# 2.net
KiCad netlist of a schematic drawn in EAGLE
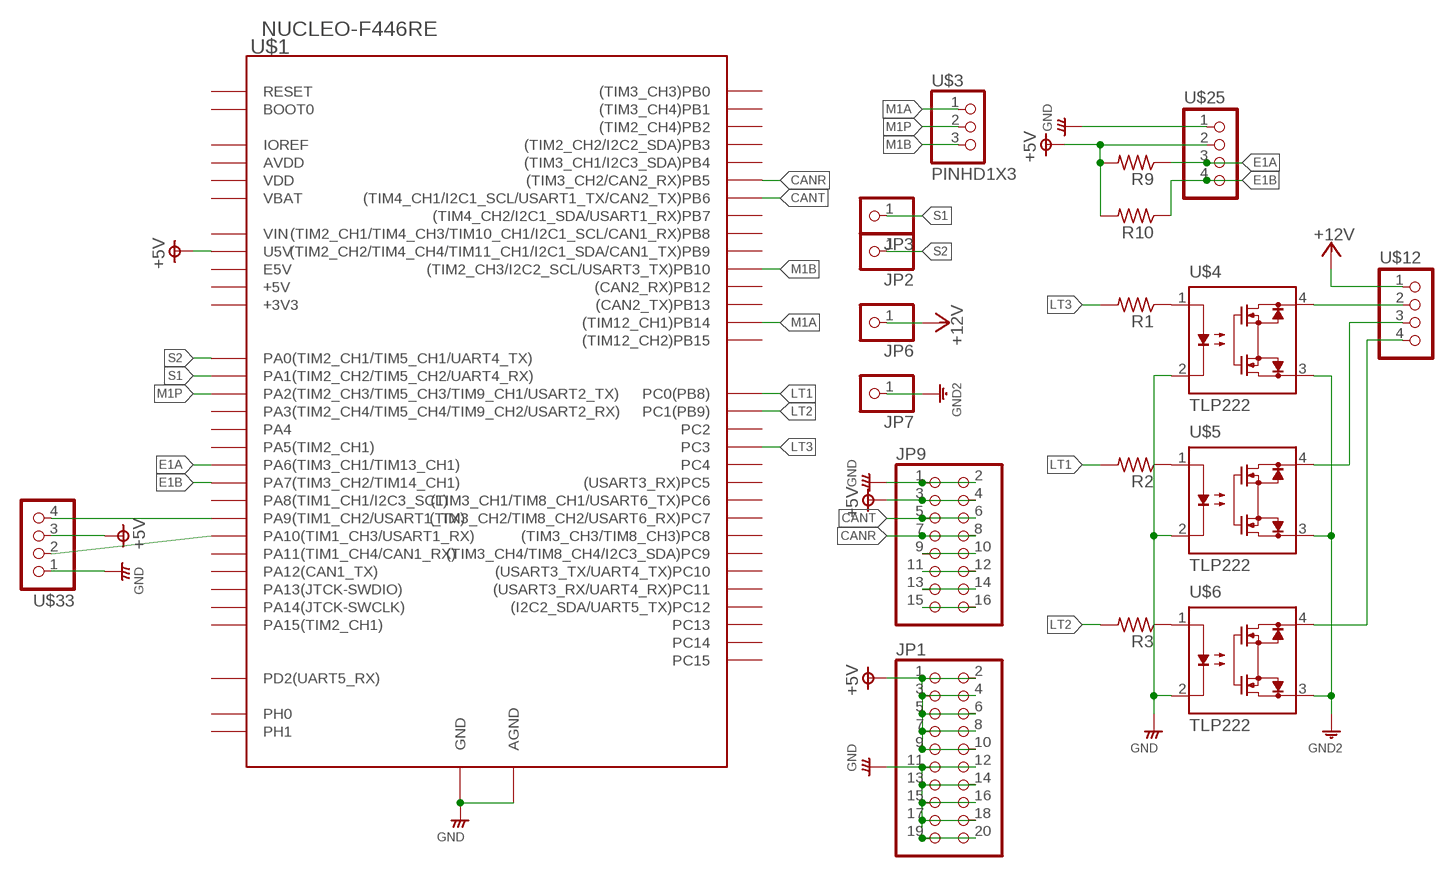
[diagram p0: schematic, sheet 1]

(export (version "E")
  (design (tool "Eeschema 10.0.6"))
  (components
    (comp (ref "JP1")
      (value "PINHD-2X10")
      (footprint "eagle-import:2X10")
      (libsource (lib "eagle-import") (part "PINHD-2X10"))
    )
    (comp (ref "JP2")
      (value "PINHD-1X1")
      (footprint "eagle-import:1X01")
      (libsource (lib "eagle-import") (part "PINHD-1X1"))
    )
    (comp (ref "JP3")
      (value "PINHD-1X1")
      (footprint "eagle-import:1X01")
      (libsource (lib "eagle-import") (part "PINHD-1X1"))
    )
    (comp (ref "JP6")
      (value "PINHD-1X1")
      (footprint "eagle-import:1X01")
      (libsource (lib "eagle-import") (part "PINHD-1X1"))
    )
    (comp (ref "JP7")
      (value "PINHD-1X1")
      (footprint "eagle-import:1X01")
      (libsource (lib "eagle-import") (part "PINHD-1X1"))
    )
    (comp (ref "JP9")
      (value "PINHD-2X8")
      (footprint "eagle-import:2X08")
      (libsource (lib "eagle-import") (part "PINHD-2X8"))
    )
    (comp (ref "R1")
      (value "RESISTORS-3")
      (footprint "eagle-import:R_0.3")
      (libsource (lib "eagle-import") (part "RESISTORS-3"))
    )
    (comp (ref "R2")
      (value "RESISTORS-3")
      (footprint "eagle-import:R_0.3")
      (libsource (lib "eagle-import") (part "RESISTORS-3"))
    )
    (comp (ref "R3")
      (value "RESISTORS-3")
      (footprint "eagle-import:R_0.3")
      (libsource (lib "eagle-import") (part "RESISTORS-3"))
    )
    (comp (ref "R9")
      (value "RESISTORS-3")
      (footprint "eagle-import:R_0.3")
      (libsource (lib "eagle-import") (part "RESISTORS-3"))
    )
    (comp (ref "R10")
      (value "RESISTORS-3")
      (footprint "eagle-import:R_0.3")
      (libsource (lib "eagle-import") (part "RESISTORS-3"))
    )
    (comp (ref "U$1")
      (value "NUCLEO-F446RE")
      (footprint "eagle-import:NUCLEO-F（L）ｘｘｘRｘ")
      (libsource (lib "eagle-import") (part "NUCLEO-F446RE"))
    )
    (comp (ref "U$3")
      (value "PINHD1X3")
      (footprint "eagle-import:1X3(XH)")
      (libsource (lib "eagle-import") (part "PINHD1X3"))
    )
    (comp (ref "U$4")
      (value "TLP222")
      (footprint "eagle-import:DIP4")
      (libsource (lib "eagle-import") (part "TLP222"))
    )
    (comp (ref "U$5")
      (value "TLP222")
      (footprint "eagle-import:DIP4")
      (libsource (lib "eagle-import") (part "TLP222"))
    )
    (comp (ref "U$6")
      (value "TLP222")
      (footprint "eagle-import:DIP4")
      (libsource (lib "eagle-import") (part "TLP222"))
    )
    (comp (ref "U$12")
      (value "XH-PIN4")
      (footprint "eagle-import:XH-4PIN")
      (libsource (lib "eagle-import") (part "XH-PIN4"))
    )
    (comp (ref "U$25")
      (value "XH-PIN4")
      (footprint "eagle-import:XH-4PIN")
      (libsource (lib "eagle-import") (part "XH-PIN4"))
    )
    (comp (ref "U$33")
      (value "XH-PIN4")
      (footprint "eagle-import:XH-4PIN")
      (libsource (lib "eagle-import") (part "XH-PIN4"))
    )
  )
  (nets
    (net (code "1") (name "+12V") (class "Default")
      (node (ref "JP6") (pin "1") (pinfunction "1_1") (pintype "passive"))
      (node (ref "U$12") (pin "1") (pinfunction "1_1") (pintype "passive"))
    )
    (net (code "2") (name "/+5V") (class "Default")
      (node (ref "JP1") (pin "1") (pinfunction "1_1") (pintype "passive"))
      (node (ref "JP1") (pin "10") (pinfunction "10_10") (pintype "passive"))
      (node (ref "JP1") (pin "2") (pinfunction "2_2") (pintype "passive"))
      (node (ref "JP1") (pin "3") (pinfunction "3_3") (pintype "passive"))
      (node (ref "JP1") (pin "4") (pinfunction "4_4") (pintype "passive"))
      (node (ref "JP1") (pin "5") (pinfunction "5_5") (pintype "passive"))
      (node (ref "JP1") (pin "6") (pinfunction "6_6") (pintype "passive"))
      (node (ref "JP1") (pin "7") (pinfunction "7_7") (pintype "passive"))
      (node (ref "JP1") (pin "8") (pinfunction "8_8") (pintype "passive"))
      (node (ref "JP1") (pin "9") (pinfunction "9_9") (pintype "passive"))
      (node (ref "JP9") (pin "3") (pinfunction "3_3") (pintype "passive"))
      (node (ref "JP9") (pin "4") (pinfunction "4_4") (pintype "passive"))
      (node (ref "R10") (pin "2") (pinfunction "2_2") (pintype "passive"))
      (node (ref "R9") (pin "2") (pinfunction "2_2") (pintype "passive"))
      (node (ref "U$1") (pin "U5V") (pinfunction "U5V_U5V") (pintype "bidirectional"))
      (node (ref "U$25") (pin "2") (pinfunction "2_2") (pintype "passive"))
      (node (ref "U$33") (pin "3") (pinfunction "3_3") (pintype "passive"))
    )
    (net (code "3") (name "CANR") (class "Default")
      (node (ref "JP9") (pin "7") (pinfunction "7_7") (pintype "passive"))
      (node (ref "JP9") (pin "8") (pinfunction "8_8") (pintype "passive"))
      (node (ref "U$1") (pin "PB5") (pinfunction "(TIM3_CH2/CAN2_RX)PB5_PB5") (pintype "bidirectional"))
    )
    (net (code "4") (name "CANT") (class "Default")
      (node (ref "JP9") (pin "5") (pinfunction "5_5") (pintype "passive"))
      (node (ref "JP9") (pin "6") (pinfunction "6_6") (pintype "passive"))
      (node (ref "U$1") (pin "PB6") (pinfunction "(TIM4_CH1/I2C1_SCL/USART1_TX/CAN2_TX)PB6_PB6") (pintype "bidirectional"))
    )
    (net (code "5") (name "E1A") (class "Default")
      (node (ref "R9") (pin "1") (pinfunction "1_1") (pintype "passive"))
      (node (ref "U$1") (pin "PA6") (pinfunction "PA6(TIM3_CH1/TIM13_CH1)_PA6") (pintype "bidirectional"))
      (node (ref "U$25") (pin "3") (pinfunction "3_3") (pintype "passive"))
    )
    (net (code "6") (name "E1B") (class "Default")
      (node (ref "R10") (pin "1") (pinfunction "1_1") (pintype "passive"))
      (node (ref "U$1") (pin "PA7") (pinfunction "PA7(TIM3_CH2/TIM14_CH1)_PA7") (pintype "bidirectional"))
      (node (ref "U$25") (pin "4") (pinfunction "4_4") (pintype "passive"))
    )
    (net (code "7") (name "GND") (class "Default")
      (node (ref "JP1") (pin "11") (pinfunction "11_11") (pintype "passive"))
      (node (ref "JP1") (pin "12") (pinfunction "12_12") (pintype "passive"))
      (node (ref "JP1") (pin "13") (pinfunction "13_13") (pintype "passive"))
      (node (ref "JP1") (pin "14") (pinfunction "14_14") (pintype "passive"))
      (node (ref "JP1") (pin "15") (pinfunction "15_15") (pintype "passive"))
      (node (ref "JP1") (pin "16") (pinfunction "16_16") (pintype "passive"))
      (node (ref "JP1") (pin "17") (pinfunction "17_17") (pintype "passive"))
      (node (ref "JP1") (pin "18") (pinfunction "18_18") (pintype "passive"))
      (node (ref "JP1") (pin "19") (pinfunction "19_19") (pintype "passive"))
      (node (ref "JP1") (pin "20") (pinfunction "20_20") (pintype "passive"))
      (node (ref "JP9") (pin "1") (pinfunction "1_1") (pintype "passive"))
      (node (ref "JP9") (pin "2") (pinfunction "2_2") (pintype "passive"))
      (node (ref "U$1") (pin "AGND") (pinfunction "AGND_AGND") (pintype "bidirectional"))
      (node (ref "U$1") (pin "GND@1") (pinfunction "GND_GND@1") (pintype "bidirectional"))
      (node (ref "U$1") (pin "GND@2") (pinfunction "GND_GND@2") (pintype "bidirectional"))
      (node (ref "U$1") (pin "GND@3") (pinfunction "GND_GND@3") (pintype "bidirectional"))
      (node (ref "U$1") (pin "GND@4") (pinfunction "GND_GND@4") (pintype "bidirectional"))
      (node (ref "U$1") (pin "GND@5") (pinfunction "GND_GND@5") (pintype "bidirectional"))
      (node (ref "U$1") (pin "GND@6") (pinfunction "GND_GND@6") (pintype "bidirectional"))
      (node (ref "U$25") (pin "1") (pinfunction "1_1") (pintype "passive"))
      (node (ref "U$33") (pin "1") (pinfunction "1_1") (pintype "passive"))
      (node (ref "U$4") (pin "2") (pinfunction "2CATHODE_2") (pintype "bidirectional"))
      (node (ref "U$5") (pin "2") (pinfunction "2CATHODE_2") (pintype "bidirectional"))
      (node (ref "U$6") (pin "2") (pinfunction "2CATHODE_2") (pintype "bidirectional"))
    )
    (net (code "8") (name "GND2") (class "Default")
      (node (ref "JP7") (pin "1") (pinfunction "1_1") (pintype "passive"))
      (node (ref "U$4") (pin "3") (pinfunction "3DRAIN_3") (pintype "bidirectional"))
      (node (ref "U$5") (pin "3") (pinfunction "3DRAIN_3") (pintype "bidirectional"))
      (node (ref "U$6") (pin "3") (pinfunction "3DRAIN_3") (pintype "bidirectional"))
    )
    (net (code "9") (name "LT1") (class "Default")
      (node (ref "R2") (pin "2") (pinfunction "2_2") (pintype "passive"))
      (node (ref "U$1") (pin "PC0") (pinfunction "PC0(PB8)_PC0") (pintype "bidirectional"))
    )
    (net (code "10") (name "LT2") (class "Default")
      (node (ref "R3") (pin "2") (pinfunction "2_2") (pintype "passive"))
      (node (ref "U$1") (pin "PC1") (pinfunction "PC1(PB9)_PC1") (pintype "bidirectional"))
    )
    (net (code "11") (name "LT3") (class "Default")
      (node (ref "R1") (pin "2") (pinfunction "2_2") (pintype "passive"))
      (node (ref "U$1") (pin "PC3") (pinfunction "PC3_PC3") (pintype "bidirectional"))
    )
    (net (code "12") (name "M1A") (class "Default")
      (node (ref "U$1") (pin "PB14") (pinfunction "(TIM12_CH1)PB14_PB14") (pintype "bidirectional"))
      (node (ref "U$3") (pin "1") (pinfunction "1_1") (pintype "passive"))
    )
    (net (code "13") (name "M1B") (class "Default")
      (node (ref "U$1") (pin "PB10") (pinfunction "(TIM2_CH3/I2C2_SCL/USART3_TX)PB10_PB10") (pintype "bidirectional"))
      (node (ref "U$3") (pin "3") (pinfunction "3_3") (pintype "passive"))
    )
    (net (code "14") (name "M1P") (class "Default")
      (node (ref "U$1") (pin "PA2") (pinfunction "PA2(TIM2_CH3/TIM5_CH3/TIM9_CH1/USART2_TX)_PA2") (pintype "bidirectional"))
      (node (ref "U$3") (pin "2") (pinfunction "2_2") (pintype "passive"))
    )
    (net (code "15") (name "Net-(JP9-Pad10)") (class "Default")
      (node (ref "JP9") (pin "10") (pinfunction "10_10") (pintype "passive"))
      (node (ref "JP9") (pin "9") (pinfunction "9_9") (pintype "passive"))
    )
    (net (code "16") (name "Net-(JP9-Pad11)") (class "Default")
      (node (ref "JP9") (pin "11") (pinfunction "11_11") (pintype "passive"))
      (node (ref "JP9") (pin "12") (pinfunction "12_12") (pintype "passive"))
    )
    (net (code "17") (name "Net-(JP9-Pad13)") (class "Default")
      (node (ref "JP9") (pin "13") (pinfunction "13_13") (pintype "passive"))
      (node (ref "JP9") (pin "14") (pinfunction "14_14") (pintype "passive"))
    )
    (net (code "18") (name "Net-(JP9-Pad15)") (class "Default")
      (node (ref "JP9") (pin "15") (pinfunction "15_15") (pintype "passive"))
      (node (ref "JP9") (pin "16") (pinfunction "16_16") (pintype "passive"))
    )
    (net (code "19") (name "Net-(U$1-PA9(TIM1_CH2{slash}USART1_TX))") (class "Default")
      (node (ref "U$1") (pin "PA9") (pinfunction "PA9(TIM1_CH2/USART1_TX)_PA9") (pintype "bidirectional"))
      (node (ref "U$33") (pin "4") (pinfunction "4_4") (pintype "passive"))
    )
    (net (code "20") (name "Net-(U$1-PA10(TIM1_CH3{slash}USART1_RX))") (class "Default")
      (node (ref "U$1") (pin "PA10") (pinfunction "PA10(TIM1_CH3/USART1_RX)_PA10") (pintype "bidirectional"))
      (node (ref "U$33") (pin "2") (pinfunction "2_2") (pintype "passive"))
    )
    (net (code "21") (name "Net-(U$4-1ANODE)") (class "Default")
      (node (ref "R1") (pin "1") (pinfunction "1_1") (pintype "passive"))
      (node (ref "U$4") (pin "1") (pinfunction "1ANODE_1") (pintype "bidirectional"))
    )
    (net (code "22") (name "Net-(U$4-4DRAIN)") (class "Default")
      (node (ref "U$12") (pin "2") (pinfunction "2_2") (pintype "passive"))
      (node (ref "U$4") (pin "4") (pinfunction "4DRAIN_4") (pintype "bidirectional"))
    )
    (net (code "23") (name "Net-(U$5-1ANODE)") (class "Default")
      (node (ref "R2") (pin "1") (pinfunction "1_1") (pintype "passive"))
      (node (ref "U$5") (pin "1") (pinfunction "1ANODE_1") (pintype "bidirectional"))
    )
    (net (code "24") (name "Net-(U$5-4DRAIN)") (class "Default")
      (node (ref "U$12") (pin "3") (pinfunction "3_3") (pintype "passive"))
      (node (ref "U$5") (pin "4") (pinfunction "4DRAIN_4") (pintype "bidirectional"))
    )
    (net (code "25") (name "Net-(U$6-1ANODE)") (class "Default")
      (node (ref "R3") (pin "1") (pinfunction "1_1") (pintype "passive"))
      (node (ref "U$6") (pin "1") (pinfunction "1ANODE_1") (pintype "bidirectional"))
    )
    (net (code "26") (name "Net-(U$6-4DRAIN)") (class "Default")
      (node (ref "U$12") (pin "4") (pinfunction "4_4") (pintype "passive"))
      (node (ref "U$6") (pin "4") (pinfunction "4DRAIN_4") (pintype "bidirectional"))
    )
    (net (code "27") (name "S1") (class "Default")
      (node (ref "JP3") (pin "1") (pinfunction "1_1") (pintype "passive"))
      (node (ref "U$1") (pin "PA1") (pinfunction "PA1(TIM2_CH2/TIM5_CH2/UART4_RX)_PA1") (pintype "bidirectional"))
    )
    (net (code "28") (name "S2") (class "Default")
      (node (ref "JP2") (pin "1") (pinfunction "1_1") (pintype "passive"))
      (node (ref "U$1") (pin "PA0") (pinfunction "PA0(TIM2_CH1/TIM5_CH1/UART4_TX)_PA0") (pintype "bidirectional"))
    )
    (net (code "29") (name "unconnected-(U$1-(CAN2_RX)PB12-PadPB12)") (class "Default")
      (node (ref "U$1") (pin "PB12") (pinfunction "(CAN2_RX)PB12_PB12") (pintype "bidirectional"))
    )
    (net (code "30") (name "unconnected-(U$1-(CAN2_TX)PB13-PadPB13)") (class "Default")
      (node (ref "U$1") (pin "PB13") (pinfunction "(CAN2_TX)PB13_PB13") (pintype "bidirectional"))
    )
    (net (code "31") (name "unconnected-(U$1-(I2C2_SDA{slash}UART5_TX)PC12-PadPC12)") (class "Default")
      (node (ref "U$1") (pin "PC12") (pinfunction "(I2C2_SDA/UART5_TX)PC12_PC12") (pintype "bidirectional"))
    )
    (net (code "32") (name "unconnected-(U$1-(TIM2_CH1{slash}TIM4_CH3{slash}TIM10_CH1{slash}I2C1_SCL{slash}CAN1_RX)PB8-PadPB8)") (class "Default")
      (node (ref "U$1") (pin "PB8") (pinfunction "(TIM2_CH1/TIM4_CH3/TIM10_CH1/I2C1_SCL/CAN1_RX)PB8_PB8") (pintype "bidirectional"))
    )
    (net (code "33") (name "unconnected-(U$1-(TIM2_CH2{slash}I2C2_SDA)PB3-PadPB3)") (class "Default")
      (node (ref "U$1") (pin "PB3") (pinfunction "(TIM2_CH2/I2C2_SDA)PB3_PB3") (pintype "bidirectional"))
    )
    (net (code "34") (name "unconnected-(U$1-(TIM2_CH2{slash}TIM4_CH4{slash}TIM11_CH1{slash}I2C1_SDA{slash}CAN1_TX)PB9-PadPB9)") (class "Default")
      (node (ref "U$1") (pin "PB9") (pinfunction "(TIM2_CH2/TIM4_CH4/TIM11_CH1/I2C1_SDA/CAN1_TX)PB9_PB9") (pintype "bidirectional"))
    )
    (net (code "35") (name "unconnected-(U$1-(TIM2_CH4)PB2-PadPB2)") (class "Default")
      (node (ref "U$1") (pin "PB2") (pinfunction "(TIM2_CH4)PB2_PB2") (pintype "bidirectional"))
    )
    (net (code "36") (name "unconnected-(U$1-(TIM3_CH1{slash}I2C3_SDA)PB4-PadPB4)") (class "Default")
      (node (ref "U$1") (pin "PB4") (pinfunction "(TIM3_CH1/I2C3_SDA)PB4_PB4") (pintype "bidirectional"))
    )
    (net (code "37") (name "unconnected-(U$1-(TIM3_CH1{slash}TIM8_CH1{slash}USART6_TX)PC6-PadPC6)") (class "Default")
      (node (ref "U$1") (pin "PC6") (pinfunction "(TIM3_CH1/TIM8_CH1/USART6_TX)PC6_PC6") (pintype "bidirectional"))
    )
    (net (code "38") (name "unconnected-(U$1-(TIM3_CH2{slash}TIM8_CH2{slash}USART6_RX)PC7-PadPC7)") (class "Default")
      (node (ref "U$1") (pin "PC7") (pinfunction "(TIM3_CH2/TIM8_CH2/USART6_RX)PC7_PC7") (pintype "bidirectional"))
    )
    (net (code "39") (name "unconnected-(U$1-(TIM3_CH3)PB0-PadPB0)") (class "Default")
      (node (ref "U$1") (pin "PB0") (pinfunction "(TIM3_CH3)PB0_PB0") (pintype "bidirectional"))
    )
    (net (code "40") (name "unconnected-(U$1-(TIM3_CH3{slash}TIM8_CH3)PC8-PadPC8)") (class "Default")
      (node (ref "U$1") (pin "PC8") (pinfunction "(TIM3_CH3/TIM8_CH3)PC8_PC8") (pintype "bidirectional"))
    )
    (net (code "41") (name "unconnected-(U$1-(TIM3_CH4)PB1-PadPB1)") (class "Default")
      (node (ref "U$1") (pin "PB1") (pinfunction "(TIM3_CH4)PB1_PB1") (pintype "bidirectional"))
    )
    (net (code "42") (name "unconnected-(U$1-(TIM3_CH4{slash}TIM8_CH4{slash}I2C3_SDA)PC9-PadPC9)") (class "Default")
      (node (ref "U$1") (pin "PC9") (pinfunction "(TIM3_CH4/TIM8_CH4/I2C3_SDA)PC9_PC9") (pintype "bidirectional"))
    )
    (net (code "43") (name "unconnected-(U$1-(TIM4_CH2{slash}I2C1_SDA{slash}USART1_RX)PB7-PadPB7)") (class "Default")
      (node (ref "U$1") (pin "PB7") (pinfunction "(TIM4_CH2/I2C1_SDA/USART1_RX)PB7_PB7") (pintype "bidirectional"))
    )
    (net (code "44") (name "unconnected-(U$1-(TIM12_CH2)PB15-PadPB15)") (class "Default")
      (node (ref "U$1") (pin "PB15") (pinfunction "(TIM12_CH2)PB15_PB15") (pintype "bidirectional"))
    )
    (net (code "45") (name "unconnected-(U$1-(USART3_RX)PC5-PadPC5)") (class "Default")
      (node (ref "U$1") (pin "PC5") (pinfunction "(USART3_RX)PC5_PC5") (pintype "bidirectional"))
    )
    (net (code "46") (name "unconnected-(U$1-(USART3_RX{slash}UART4_RX)PC11-PadPC11)") (class "Default")
      (node (ref "U$1") (pin "PC11") (pinfunction "(USART3_RX/UART4_RX)PC11_PC11") (pintype "bidirectional"))
    )
    (net (code "47") (name "unconnected-(U$1-(USART3_TX{slash}UART4_TX)PC10-PadPC10)") (class "Default")
      (node (ref "U$1") (pin "PC10") (pinfunction "(USART3_TX/UART4_TX)PC10_PC10") (pintype "bidirectional"))
    )
    (net (code "48") (name "unconnected-(U$1-PA3(TIM2_CH4{slash}TIM5_CH4{slash}TIM9_CH2{slash}USART2_RX)-PadPA3)") (class "Default")
      (node (ref "U$1") (pin "PA3") (pinfunction "PA3(TIM2_CH4/TIM5_CH4/TIM9_CH2/USART2_RX)_PA3") (pintype "bidirectional"))
    )
    (net (code "49") (name "unconnected-(U$1-PA5(TIM2_CH1)-PadPA5)") (class "Default")
      (node (ref "U$1") (pin "PA5") (pinfunction "PA5(TIM2_CH1)_PA5") (pintype "bidirectional"))
    )
    (net (code "50") (name "unconnected-(U$1-PA8(TIM1_CH1{slash}I2C3_SCL)-PadPA8)") (class "Default")
      (node (ref "U$1") (pin "PA8") (pinfunction "PA8(TIM1_CH1/I2C3_SCL)_PA8") (pintype "bidirectional"))
    )
    (net (code "51") (name "unconnected-(U$1-PA11(TIM1_CH4{slash}CAN1_RX)-PadPA11)") (class "Default")
      (node (ref "U$1") (pin "PA11") (pinfunction "PA11(TIM1_CH4/CAN1_RX)_PA11") (pintype "bidirectional"))
    )
    (net (code "52") (name "unconnected-(U$1-PA12(CAN1_TX)-PadPA12)") (class "Default")
      (node (ref "U$1") (pin "PA12") (pinfunction "PA12(CAN1_TX)_PA12") (pintype "bidirectional"))
    )
    (net (code "53") (name "unconnected-(U$1-PA13(JTCK-SWDIO)-PadPA13)") (class "Default")
      (node (ref "U$1") (pin "PA13") (pinfunction "PA13(JTCK-SWDIO)_PA13") (pintype "bidirectional"))
    )
    (net (code "54") (name "unconnected-(U$1-PA14(JTCK-SWCLK)-PadPA14)") (class "Default")
      (node (ref "U$1") (pin "PA14") (pinfunction "PA14(JTCK-SWCLK)_PA14") (pintype "bidirectional"))
    )
    (net (code "55") (name "unconnected-(U$1-PA15(TIM2_CH1)-PadPA15)") (class "Default")
      (node (ref "U$1") (pin "PA15") (pinfunction "PA15(TIM2_CH1)_PA15") (pintype "bidirectional"))
    )
    (net (code "56") (name "unconnected-(U$1-PD2(UART5_RX)-PadPD2)") (class "Default")
      (node (ref "U$1") (pin "PD2") (pinfunction "PD2(UART5_RX)_PD2") (pintype "bidirectional"))
    )
    (net (code "57") (name "unconnected-(U$1-Pad+3V3)") (class "Default")
      (node (ref "U$1") (pin "+3V3") (pinfunction "+3V3_+3V3") (pintype "bidirectional"))
    )
    (net (code "58") (name "unconnected-(U$1-Pad+5V)") (class "Default")
      (node (ref "U$1") (pin "+5V") (pinfunction "+5V_+5V") (pintype "bidirectional"))
    )
    (net (code "59") (name "unconnected-(U$1-PadAVDD)") (class "Default")
      (node (ref "U$1") (pin "AVDD") (pinfunction "AVDD_AVDD") (pintype "bidirectional"))
    )
    (net (code "60") (name "unconnected-(U$1-PadBOOT0)") (class "Default")
      (node (ref "U$1") (pin "BOOT0") (pinfunction "BOOT0_BOOT0") (pintype "bidirectional"))
    )
    (net (code "61") (name "unconnected-(U$1-PadE5V)") (class "Default")
      (node (ref "U$1") (pin "E5V") (pinfunction "E5V_E5V") (pintype "bidirectional"))
    )
    (net (code "62") (name "unconnected-(U$1-PadIOREF)") (class "Default")
      (node (ref "U$1") (pin "IOREF") (pinfunction "IOREF_IOREF") (pintype "bidirectional"))
    )
    (net (code "63") (name "unconnected-(U$1-PadPA4)") (class "Default")
      (node (ref "U$1") (pin "PA4") (pinfunction "PA4_PA4") (pintype "bidirectional"))
    )
    (net (code "64") (name "unconnected-(U$1-PadPC2)") (class "Default")
      (node (ref "U$1") (pin "PC2") (pinfunction "PC2_PC2") (pintype "bidirectional"))
    )
    (net (code "65") (name "unconnected-(U$1-PadPC4)") (class "Default")
      (node (ref "U$1") (pin "PC4") (pinfunction "PC4_PC4") (pintype "bidirectional"))
    )
    (net (code "66") (name "unconnected-(U$1-PadPC13)") (class "Default")
      (node (ref "U$1") (pin "PC13") (pinfunction "PC13_PC13") (pintype "bidirectional"))
    )
    (net (code "67") (name "unconnected-(U$1-PadPC14)") (class "Default")
      (node (ref "U$1") (pin "PC14") (pinfunction "PC14_PC14") (pintype "bidirectional"))
    )
    (net (code "68") (name "unconnected-(U$1-PadPC15)") (class "Default")
      (node (ref "U$1") (pin "PC15") (pinfunction "PC15_PC15") (pintype "bidirectional"))
    )
    (net (code "69") (name "unconnected-(U$1-PadPH0)") (class "Default")
      (node (ref "U$1") (pin "PH0") (pinfunction "PH0_PH0") (pintype "bidirectional"))
    )
    (net (code "70") (name "unconnected-(U$1-PadPH1)") (class "Default")
      (node (ref "U$1") (pin "PH1") (pinfunction "PH1_PH1") (pintype "bidirectional"))
    )
    (net (code "71") (name "unconnected-(U$1-PadRESET)") (class "Default")
      (node (ref "U$1") (pin "RESET") (pinfunction "RESET_RESET") (pintype "bidirectional"))
    )
    (net (code "72") (name "unconnected-(U$1-PadVBAT)") (class "Default")
      (node (ref "U$1") (pin "VBAT") (pinfunction "VBAT_VBAT") (pintype "bidirectional"))
    )
    (net (code "73") (name "unconnected-(U$1-PadVDD)") (class "Default")
      (node (ref "U$1") (pin "VDD") (pinfunction "VDD_VDD") (pintype "bidirectional"))
    )
    (net (code "74") (name "unconnected-(U$1-PadVIN)") (class "Default")
      (node (ref "U$1") (pin "VIN") (pinfunction "VIN_VIN") (pintype "bidirectional"))
    )
  )
)
